# Relay_Schem_NC.net
KiCad netlist of a schematic drawn in Altium Designer
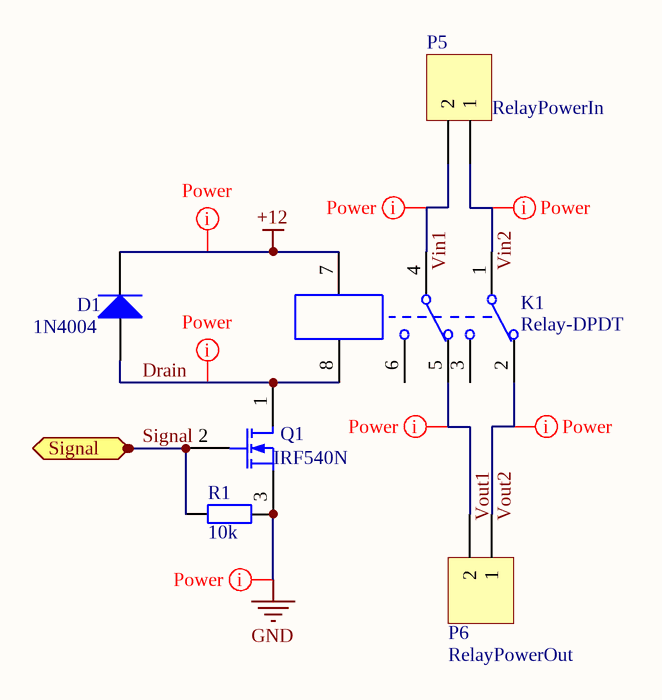
[diagram p0: Relay_Schem_NC.SchDoc]

(export (version "E")
  (design (tool "Eeschema 10.0.6"))
  (components
    (comp (ref "D1")
      (value "1N4004")
      (footprint "DIODE-0.3-SI")
      (description "1 Amp General Purpose Rectifier")
      (fields (field (name "PUBLISHER") "Altium Limited"))
      (libsource (lib "Miscellaneous Devices") (part "Diode 1N4005"))
    )
    (comp (ref "K1")
      (value "Relay-DPDT")
      (footprint "Relay_95.12 Socket - With Screw")
      (description "Dual-Pole Dual-Throw Relay")
      (fields (field (name "PUBLISHER") "Altium Limited"))
      (libsource (lib "Miscellaneous Devices") (part "Relay-DPDT"))
    )
    (comp (ref "P5")
      (value "RelayPowerIn")
      (footprint "CONN-WAFER-2x1")
      (description "Header, 2-Pin")
      (fields (field (name "PUBLISHER") "Altium Limited"))
      (libsource (lib "Miscellaneous Connectors") (part "Header 2"))
    )
    (comp (ref "P6")
      (value "RelayPowerOut")
      (footprint "CONN-WAFER-2x1")
      (description "Header, 2-Pin")
      (fields (field (name "PUBLISHER") "Altium Limited"))
      (libsource (lib "") (part "Header 2_1"))
    )
    (comp (ref "Q1")
      (value "IRF540N")
      (footprint "TO-220")
      (description "N-Channel MOSFET")
      (fields (field (name "PUBLISHER") "Altium Limited"))
      (libsource (lib "Miscellaneous Devices") (part "MOSFET-N"))
    )
    (comp (ref "R1")
      (value "10k")
      (footprint "RES-0.4")
      (description "Resistor")
      (fields (field (name "PUBLISHER") "Altium Limited"))
      (libsource (lib "Miscellaneous Devices") (part "Res2"))
    )
  )
  (nets
    (net (code "1") (name "+12") (class "Default")
      (node (ref "D1") (pin "2") (pinfunction "K_2") (pintype "passive"))
      (node (ref "K1") (pin "7") (pinfunction "7_7") (pintype "passive"))
    )
    (net (code "2") (name "/Drain") (class "Default")
      (node (ref "D1") (pin "1") (pinfunction "A_1") (pintype "passive"))
      (node (ref "K1") (pin "8") (pinfunction "8_8") (pintype "passive"))
      (node (ref "Q1") (pin "1") (pinfunction "D_1") (pintype "passive"))
    )
    (net (code "3") (name "/Signal") (class "Default")
      (node (ref "Q1") (pin "2") (pinfunction "G_2") (pintype "passive"))
      (node (ref "R1") (pin "1") (pinfunction "1_1") (pintype "passive"))
    )
    (net (code "4") (name "/Vin1") (class "Default")
      (node (ref "K1") (pin "4") (pinfunction "4_4") (pintype "passive"))
      (node (ref "P5") (pin "2") (pinfunction "2_2") (pintype "passive"))
    )
    (net (code "5") (name "/Vin2") (class "Default")
      (node (ref "K1") (pin "1") (pinfunction "1_1") (pintype "passive"))
      (node (ref "P5") (pin "1") (pinfunction "1_1") (pintype "passive"))
    )
    (net (code "6") (name "/Vout1") (class "Default")
      (node (ref "K1") (pin "5") (pinfunction "5_5") (pintype "passive"))
      (node (ref "P6") (pin "2") (pinfunction "2_2") (pintype "passive"))
    )
    (net (code "7") (name "/Vout2") (class "Default")
      (node (ref "K1") (pin "2") (pinfunction "2_2") (pintype "passive"))
      (node (ref "P6") (pin "1") (pinfunction "1_1") (pintype "passive"))
    )
    (net (code "8") (name "GND") (class "Default")
      (node (ref "Q1") (pin "3") (pinfunction "S_3") (pintype "passive"))
      (node (ref "R1") (pin "2") (pinfunction "2_2") (pintype "passive"))
    )
    (net (code "9") (name "unconnected-(K1-Pad3)") (class "Default")
      (node (ref "K1") (pin "3") (pinfunction "3_3") (pintype "passive"))
    )
    (net (code "10") (name "unconnected-(K1-Pad6)") (class "Default")
      (node (ref "K1") (pin "6") (pinfunction "6_6") (pintype "passive"))
    )
  )
)
